# rtu04.net
KiCad netlist of a schematic drawn in EAGLE
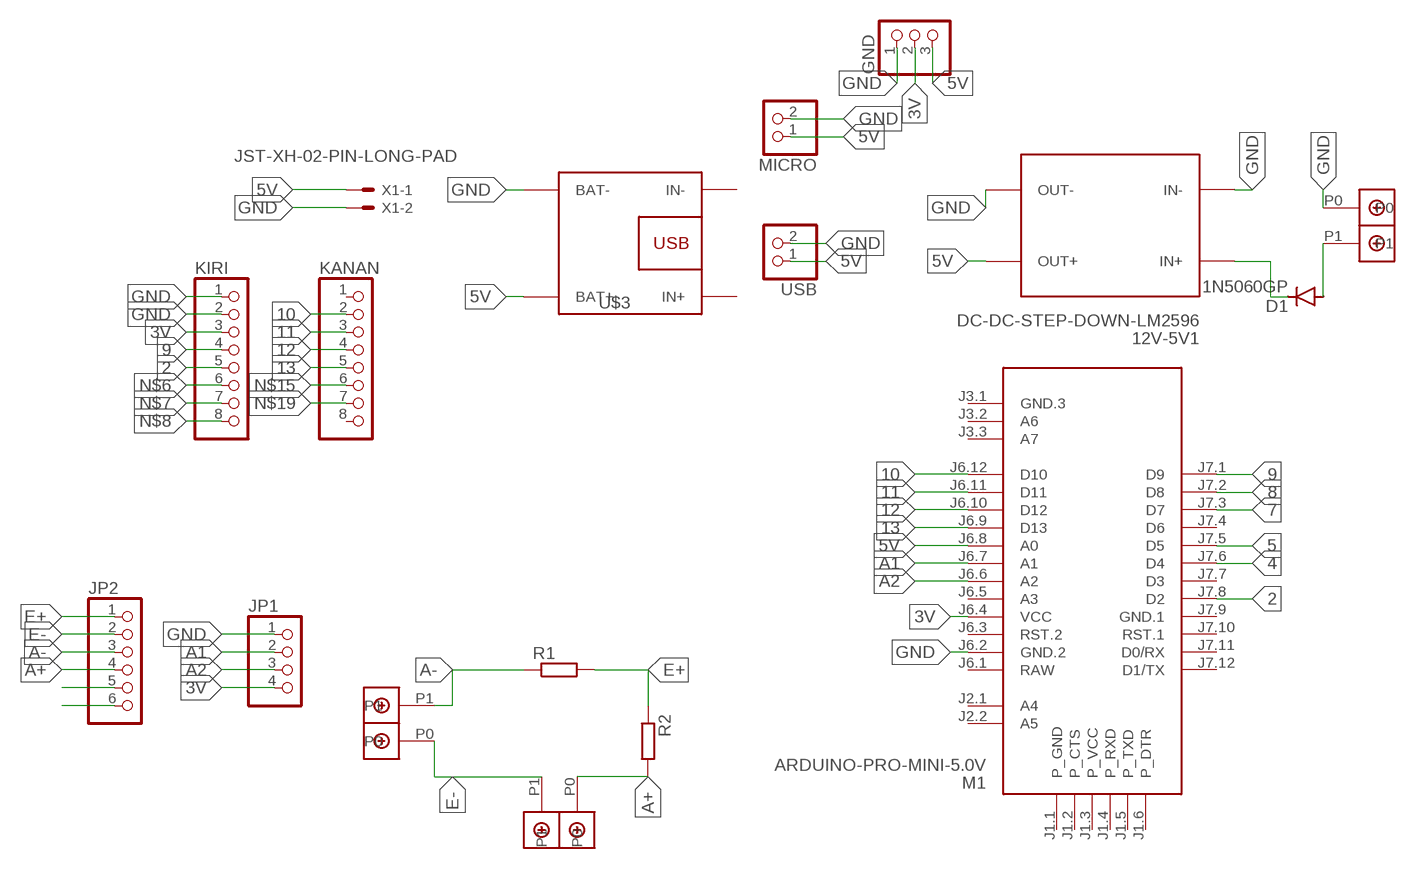
[diagram p0: schematic, sheet 1]

(export (version "E")
  (design (tool "Eeschema 10.0.6"))
  (components
    (comp (ref "12V-5V1")
      (value "DC-DC-STEP-DOWN-LM2596")
      (footprint "eagle-import:DC-DC-STEP-DOWN-LM2596")
      (libsource (lib "eagle-import") (part "DC-DC-STEP-DOWN-LM2596"))
    )
    (comp (ref "D1")
      (value "1N5060GP")
      (footprint "eagle-import:DO15-12")
      (libsource (lib "eagle-import") (part "1N5060GP"))
    )
    (comp (ref "GND")
      (value "PINHD-1X3")
      (footprint "eagle-import:1X03")
      (libsource (lib "eagle-import") (part "PINHD-1X3"))
    )
    (comp (ref "JP1")
      (value "PINHD-1X4")
      (footprint "eagle-import:1X04")
      (libsource (lib "eagle-import") (part "PINHD-1X4"))
    )
    (comp (ref "JP2")
      (value "PINHD-1X6")
      (footprint "eagle-import:1X06")
      (libsource (lib "eagle-import") (part "PINHD-1X6"))
    )
    (comp (ref "KANAN")
      (value "PINHD-1X8")
      (footprint "eagle-import:1X08")
      (libsource (lib "eagle-import") (part "PINHD-1X8"))
    )
    (comp (ref "KIRI")
      (value "PINHD-1X8")
      (footprint "eagle-import:1X08")
      (libsource (lib "eagle-import") (part "PINHD-1X8"))
    )
    (comp (ref "M1")
      (value "ARDUINO-PRO-MINI-5.0V")
      (footprint "eagle-import:ARDUINO-PRO-MINI")
      (libsource (lib "eagle-import") (part "ARDUINO-PRO-MINI-5.0V"))
    )
    (comp (ref "MICRO")
      (value "PINHD-1X2")
      (footprint "eagle-import:1X02")
      (libsource (lib "eagle-import") (part "PINHD-1X2"))
    )
    (comp (ref "R1")
      (value "R-EU_0207/10")
      (footprint "eagle-import:0207_10")
      (libsource (lib "eagle-import") (part "R-EU_0207/10"))
    )
    (comp (ref "R2")
      (value "R-EU_0207/10")
      (footprint "eagle-import:0207_10")
      (libsource (lib "eagle-import") (part "R-EU_0207/10"))
    )
    (comp (ref "U$1")
      (value "DBCONN-1X2")
      (footprint "eagle-import:DBCONN-1X2")
      (libsource (lib "eagle-import") (part "DBCONN-1X2"))
    )
    (comp (ref "U$2")
      (value "DBCONN-1X2")
      (footprint "eagle-import:DBCONN-1X2")
      (libsource (lib "eagle-import") (part "DBCONN-1X2"))
    )
    (comp (ref "U$3")
      (value "BATTERY-CHARGER-LI-5V")
      (footprint "eagle-import:BATTERY-CHARGER-LI-5V")
      (libsource (lib "eagle-import") (part "BATTERY-CHARGER-LI-5V"))
    )
    (comp (ref "U$4")
      (value "DBCONN-1X2")
      (footprint "eagle-import:DBCONN-1X2")
      (libsource (lib "eagle-import") (part "DBCONN-1X2"))
    )
    (comp (ref "USB")
      (value "PINHD-1X2")
      (footprint "eagle-import:1X02")
      (libsource (lib "eagle-import") (part "PINHD-1X2"))
    )
    (comp (ref "X1")
      (value "JST-XH-02-PIN-LONG-PAD")
      (footprint "eagle-import:JST-XH-02-PACKAGE-LONG-PAD")
      (libsource (lib "eagle-import") (part "JST-XH-02-PIN-LONG-PAD"))
    )
  )
  (nets
    (net (code "1") (name "/GND.1") (class "Default")
      (node (ref "M1") (pin "J7.9") (pinfunction "GND.1_J7.9") (pintype "power_in"))
    )
    (net (code "2") (name "/RAW") (class "Default")
      (node (ref "M1") (pin "J6.1") (pinfunction "RAW_J6.1") (pintype "power_in"))
    )
    (net (code "3") (name "2") (class "Default")
      (node (ref "KIRI") (pin "5") (pinfunction "5_5") (pintype "passive"))
      (node (ref "M1") (pin "J7.8") (pinfunction "D2_J7.8") (pintype "bidirectional"))
    )
    (net (code "4") (name "3V") (class "Default")
      (node (ref "GND") (pin "2") (pinfunction "2_2") (pintype "passive"))
      (node (ref "JP1") (pin "4") (pinfunction "4_4") (pintype "passive"))
      (node (ref "KIRI") (pin "3") (pinfunction "3_3") (pintype "passive"))
      (node (ref "M1") (pin "J6.4") (pinfunction "VCC_J6.4") (pintype "power_in"))
    )
    (net (code "5") (name "4") (class "Default")
      (node (ref "M1") (pin "J7.6") (pinfunction "D4_J7.6") (pintype "bidirectional"))
    )
    (net (code "6") (name "5") (class "Default")
      (node (ref "M1") (pin "J7.5") (pinfunction "D5_J7.5") (pintype "bidirectional"))
    )
    (net (code "7") (name "5V") (class "Default")
      (node (ref "12V-5V1") (pin "OUT+") (pinfunction "OUT+_OUT+") (pintype "bidirectional"))
      (node (ref "GND") (pin "3") (pinfunction "3_3") (pintype "passive"))
      (node (ref "M1") (pin "J6.8") (pinfunction "A0_J6.8") (pintype "bidirectional"))
      (node (ref "MICRO") (pin "1") (pinfunction "1_1") (pintype "passive"))
      (node (ref "U$3") (pin "BAT+") (pinfunction "BAT+_BAT+") (pintype "bidirectional"))
      (node (ref "USB") (pin "1") (pinfunction "1_1") (pintype "passive"))
      (node (ref "X1") (pin "1") (pinfunction "S_1") (pintype "passive"))
    )
    (net (code "8") (name "7") (class "Default")
      (node (ref "M1") (pin "J7.3") (pinfunction "D7_J7.3") (pintype "bidirectional"))
    )
    (net (code "9") (name "8") (class "Default")
      (node (ref "M1") (pin "J7.2") (pinfunction "D8_J7.2") (pintype "bidirectional"))
    )
    (net (code "10") (name "9") (class "Default")
      (node (ref "KIRI") (pin "4") (pinfunction "4_4") (pintype "passive"))
      (node (ref "M1") (pin "J7.1") (pinfunction "D9_J7.1") (pintype "bidirectional"))
    )
    (net (code "11") (name "10") (class "Default")
      (node (ref "KANAN") (pin "2") (pinfunction "2_2") (pintype "passive"))
      (node (ref "M1") (pin "J6.12") (pinfunction "D10_J6.12") (pintype "bidirectional"))
    )
    (net (code "12") (name "11") (class "Default")
      (node (ref "KANAN") (pin "3") (pinfunction "3_3") (pintype "passive"))
      (node (ref "M1") (pin "J6.11") (pinfunction "D11_J6.11") (pintype "bidirectional"))
    )
    (net (code "13") (name "12") (class "Default")
      (node (ref "KANAN") (pin "4") (pinfunction "4_4") (pintype "passive"))
      (node (ref "M1") (pin "J6.10") (pinfunction "D12_J6.10") (pintype "bidirectional"))
    )
    (net (code "14") (name "13") (class "Default")
      (node (ref "KANAN") (pin "5") (pinfunction "5_5") (pintype "passive"))
      (node (ref "M1") (pin "J6.9") (pinfunction "D13_J6.9") (pintype "bidirectional"))
    )
    (net (code "15") (name "A+") (class "Default")
      (node (ref "JP2") (pin "4") (pinfunction "4_4") (pintype "passive"))
      (node (ref "R2") (pin "2") (pinfunction "2_2") (pintype "passive"))
      (node (ref "U$2") (pin "P0") (pinfunction "P0_P0") (pintype "bidirectional"))
    )
    (net (code "16") (name "A-") (class "Default")
      (node (ref "JP2") (pin "3") (pinfunction "3_3") (pintype "passive"))
      (node (ref "R1") (pin "1") (pinfunction "1_1") (pintype "passive"))
      (node (ref "U$4") (pin "P1") (pinfunction "P1_P1") (pintype "bidirectional"))
    )
    (net (code "17") (name "A1") (class "Default")
      (node (ref "JP1") (pin "2") (pinfunction "2_2") (pintype "passive"))
      (node (ref "M1") (pin "J6.7") (pinfunction "A1_J6.7") (pintype "bidirectional"))
    )
    (net (code "18") (name "A2") (class "Default")
      (node (ref "JP1") (pin "3") (pinfunction "3_3") (pintype "passive"))
      (node (ref "M1") (pin "J6.6") (pinfunction "A2_J6.6") (pintype "bidirectional"))
    )
    (net (code "19") (name "E+") (class "Default")
      (node (ref "JP2") (pin "1") (pinfunction "1_1") (pintype "passive"))
      (node (ref "R1") (pin "2") (pinfunction "2_2") (pintype "passive"))
      (node (ref "R2") (pin "1") (pinfunction "1_1") (pintype "passive"))
    )
    (net (code "20") (name "E-") (class "Default")
      (node (ref "JP2") (pin "2") (pinfunction "2_2") (pintype "passive"))
      (node (ref "U$2") (pin "P1") (pinfunction "P1_P1") (pintype "bidirectional"))
      (node (ref "U$4") (pin "P0") (pinfunction "P0_P0") (pintype "bidirectional"))
    )
    (net (code "21") (name "GND") (class "Default")
      (node (ref "12V-5V1") (pin "IN-") (pinfunction "IN-_IN-") (pintype "bidirectional"))
      (node (ref "12V-5V1") (pin "OUT-") (pinfunction "OUT-_OUT-") (pintype "bidirectional"))
      (node (ref "GND") (pin "1") (pinfunction "1_1") (pintype "passive"))
      (node (ref "JP1") (pin "1") (pinfunction "1_1") (pintype "passive"))
      (node (ref "KIRI") (pin "1") (pinfunction "1_1") (pintype "passive"))
      (node (ref "KIRI") (pin "2") (pinfunction "2_2") (pintype "passive"))
      (node (ref "M1") (pin "J6.2") (pinfunction "GND.2_J6.2") (pintype "power_in"))
      (node (ref "MICRO") (pin "2") (pinfunction "2_2") (pintype "passive"))
      (node (ref "U$1") (pin "P0") (pinfunction "P0_P0") (pintype "bidirectional"))
      (node (ref "U$3") (pin "BAT-") (pinfunction "BAT-_BAT-") (pintype "bidirectional"))
      (node (ref "USB") (pin "2") (pinfunction "2_2") (pintype "passive"))
      (node (ref "X1") (pin "2") (pinfunction "S_2") (pintype "passive"))
    )
    (net (code "22") (name "N$6") (class "Default")
      (node (ref "KIRI") (pin "6") (pinfunction "6_6") (pintype "passive"))
    )
    (net (code "23") (name "N$7") (class "Default")
      (node (ref "KIRI") (pin "7") (pinfunction "7_7") (pintype "passive"))
    )
    (net (code "24") (name "N$8") (class "Default")
      (node (ref "KIRI") (pin "8") (pinfunction "8_8") (pintype "passive"))
    )
    (net (code "25") (name "N$15") (class "Default")
      (node (ref "KANAN") (pin "6") (pinfunction "6_6") (pintype "passive"))
    )
    (net (code "26") (name "N$19") (class "Default")
      (node (ref "KANAN") (pin "7") (pinfunction "7_7") (pintype "passive"))
    )
    (net (code "27") (name "Net-(12V-5V1-PadIN+)") (class "Default")
      (node (ref "12V-5V1") (pin "IN+") (pinfunction "IN+_IN+") (pintype "bidirectional"))
      (node (ref "D1") (pin "C") (pinfunction "C_C") (pintype "passive"))
    )
    (net (code "28") (name "Net-(D1-PadA)") (class "Default")
      (node (ref "D1") (pin "A") (pinfunction "A_A") (pintype "passive"))
      (node (ref "U$1") (pin "P1") (pinfunction "P1_P1") (pintype "bidirectional"))
    )
    (net (code "29") (name "unconnected-(JP2-Pad5)") (class "Default")
      (node (ref "JP2") (pin "5") (pinfunction "5_5") (pintype "passive"))
    )
    (net (code "30") (name "unconnected-(JP2-Pad6)") (class "Default")
      (node (ref "JP2") (pin "6") (pinfunction "6_6") (pintype "passive"))
    )
    (net (code "31") (name "unconnected-(KANAN-Pad1)") (class "Default")
      (node (ref "KANAN") (pin "1") (pinfunction "1_1") (pintype "passive"))
    )
    (net (code "32") (name "unconnected-(KANAN-Pad8)") (class "Default")
      (node (ref "KANAN") (pin "8") (pinfunction "8_8") (pintype "passive"))
    )
    (net (code "33") (name "unconnected-(M1-A3-PadJ6.5)") (class "Default")
      (node (ref "M1") (pin "J6.5") (pinfunction "A3_J6.5") (pintype "bidirectional"))
    )
    (net (code "34") (name "unconnected-(M1-A4-PadJ2.1)") (class "Default")
      (node (ref "M1") (pin "J2.1") (pinfunction "A4_J2.1") (pintype "bidirectional"))
    )
    (net (code "35") (name "unconnected-(M1-A5-PadJ2.2)") (class "Default")
      (node (ref "M1") (pin "J2.2") (pinfunction "A5_J2.2") (pintype "bidirectional"))
    )
    (net (code "36") (name "unconnected-(M1-A6-PadJ3.2)") (class "Default")
      (node (ref "M1") (pin "J3.2") (pinfunction "A6_J3.2") (pintype "bidirectional"))
    )
    (net (code "37") (name "unconnected-(M1-A7-PadJ3.3)") (class "Default")
      (node (ref "M1") (pin "J3.3") (pinfunction "A7_J3.3") (pintype "bidirectional"))
    )
    (net (code "38") (name "unconnected-(M1-D0{slash}RX-PadJ7.11)") (class "Default")
      (node (ref "M1") (pin "J7.11") (pinfunction "D0/RX_J7.11") (pintype "bidirectional"))
    )
    (net (code "39") (name "unconnected-(M1-D1{slash}TX-PadJ7.12)") (class "Default")
      (node (ref "M1") (pin "J7.12") (pinfunction "D1/TX_J7.12") (pintype "bidirectional"))
    )
    (net (code "40") (name "unconnected-(M1-D3-PadJ7.7)") (class "Default")
      (node (ref "M1") (pin "J7.7") (pinfunction "D3_J7.7") (pintype "bidirectional"))
    )
    (net (code "41") (name "unconnected-(M1-D6-PadJ7.4)") (class "Default")
      (node (ref "M1") (pin "J7.4") (pinfunction "D6_J7.4") (pintype "bidirectional"))
    )
    (net (code "42") (name "unconnected-(M1-GND.3-PadJ3.1)") (class "Default")
      (node (ref "M1") (pin "J3.1") (pinfunction "GND.3_J3.1") (pintype "bidirectional"))
    )
    (net (code "43") (name "unconnected-(M1-P_CTS-PadJ1.2)") (class "Default")
      (node (ref "M1") (pin "J1.2") (pinfunction "P_CTS_J1.2") (pintype "bidirectional"))
    )
    (net (code "44") (name "unconnected-(M1-P_DTR-PadJ1.6)") (class "Default")
      (node (ref "M1") (pin "J1.6") (pinfunction "P_DTR_J1.6") (pintype "bidirectional"))
    )
    (net (code "45") (name "unconnected-(M1-P_GND-PadJ1.1)") (class "Default")
      (node (ref "M1") (pin "J1.1") (pinfunction "P_GND_J1.1") (pintype "bidirectional"))
    )
    (net (code "46") (name "unconnected-(M1-P_RXD-PadJ1.4)") (class "Default")
      (node (ref "M1") (pin "J1.4") (pinfunction "P_RXD_J1.4") (pintype "bidirectional"))
    )
    (net (code "47") (name "unconnected-(M1-P_TXD-PadJ1.5)") (class "Default")
      (node (ref "M1") (pin "J1.5") (pinfunction "P_TXD_J1.5") (pintype "bidirectional"))
    )
    (net (code "48") (name "unconnected-(M1-P_VCC-PadJ1.3)") (class "Default")
      (node (ref "M1") (pin "J1.3") (pinfunction "P_VCC_J1.3") (pintype "bidirectional"))
    )
    (net (code "49") (name "unconnected-(M1-RST.1-PadJ7.10)") (class "Default")
      (node (ref "M1") (pin "J7.10") (pinfunction "RST.1_J7.10") (pintype "bidirectional"))
    )
    (net (code "50") (name "unconnected-(M1-RST.2-PadJ6.3)") (class "Default")
      (node (ref "M1") (pin "J6.3") (pinfunction "RST.2_J6.3") (pintype "bidirectional"))
    )
    (net (code "51") (name "unconnected-(U$3-PadIN+)") (class "Default")
      (node (ref "U$3") (pin "IN+") (pinfunction "IN+_IN+") (pintype "bidirectional"))
    )
    (net (code "52") (name "unconnected-(U$3-PadIN-)") (class "Default")
      (node (ref "U$3") (pin "IN-") (pinfunction "IN-_IN-") (pintype "bidirectional"))
    )
  )
)
